# GPS_L70.net
KiCad netlist of a schematic drawn in Altium Designer
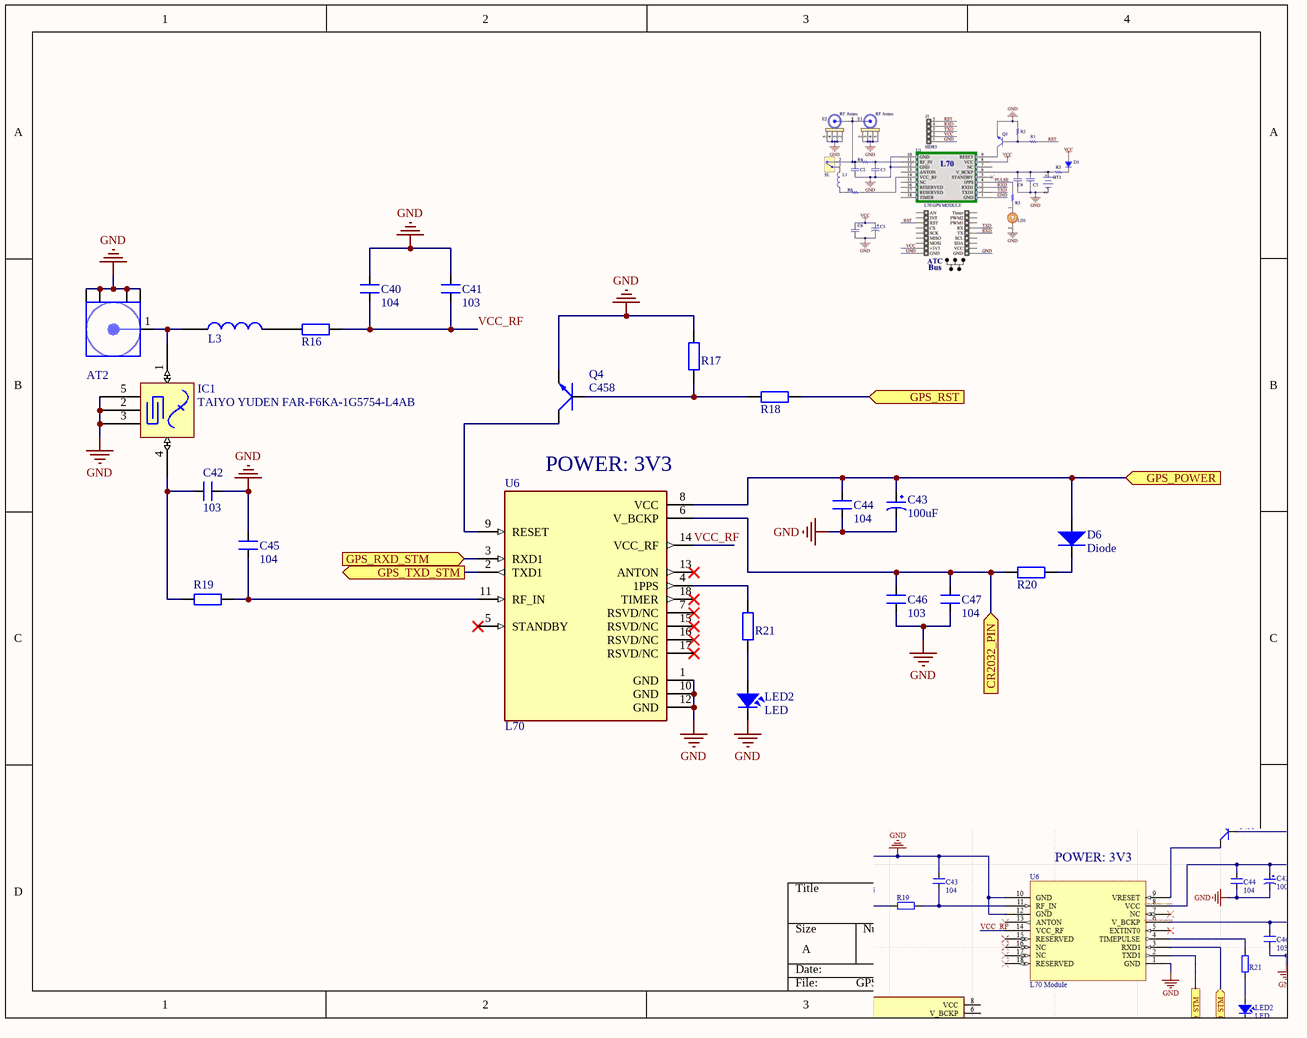
[diagram p0: GPS_L70.SchDoc]

(export (version "E")
  (design (tool "Eeschema 10.0.6"))
  (components
    (comp (ref "AT2")
      (value "AT-GSM-GPS")
      (footprint "SNW_H13-L17-SMA")
      (description "CONNECTER ANTENNA GPS GSM")
      (fields (field (name "MPN") "SNW_H13-L17-SMA") (field (name "MFR") "Sunny Way"))
      (libsource (lib "BYTECH_HW_LIB_2019 (1)") (part "SNW_H13-L17-SMA"))
    )
    (comp (ref "C40")
      (value "104")
      (footprint "CN2")
      (description "Cap np 104 => 105pF")
      (libsource (lib "KhanhBK_Library_4") (part "CN2"))
    )
    (comp (ref "C41")
      (value "103")
      (footprint "SM-0805")
      (description "Cap SMD")
      (libsource (lib "KhanhBK_Library_4") (part "CM"))
    )
    (comp (ref "C42")
      (value "103")
      (footprint "SM-0805")
      (description "Cap SMD")
      (libsource (lib "KhanhBK_Library_4") (part "CM"))
    )
    (comp (ref "C43")
      (value "100uF")
      (footprint "CP1/2.5")
      (description "C 47uF/50V , 220uF/16V")
      (libsource (lib "KhanhBK_Library_4") (part "CP2"))
    )
    (comp (ref "C44")
      (value "104")
      (footprint "CN2")
      (description "Cap np 104 => 105pF")
      (libsource (lib "KhanhBK_Library_4") (part "CN2"))
    )
    (comp (ref "C45")
      (value "104")
      (footprint "CN2")
      (description "Cap np 104 => 105pF")
      (libsource (lib "KhanhBK_Library_4") (part "CN2"))
    )
    (comp (ref "C46")
      (value "103")
      (footprint "SM-0805")
      (description "Cap SMD")
      (libsource (lib "KhanhBK_Library_4") (part "CM"))
    )
    (comp (ref "C47")
      (value "104")
      (footprint "CN2")
      (description "Cap np 104 => 105pF")
      (libsource (lib "KhanhBK_Library_4") (part "CN2"))
    )
    (comp (ref "D6")
      (value "Diode")
      (footprint "DIO-SMD-106")
      (libsource (lib "KhanhBK_Library_4") (part "Diode"))
    )
    (comp (ref "IC1")
      (value "TAIYO YUDEN FAR-F6KA-1G5754-L4AB")
      (footprint "TAIYO YUDEN SMD-5 1.4x1mm")
      (description "GPS SAW Filter Taiyo Yuden")
      (libsource (lib "KhanhBK_Library_4") (part "TAIYO YUDEN FAR-F6KA-1G5754-L4AB"))
    )
    (comp (ref "L3")
      (value "15uH/850mA")
      (footprint "IND-1210 (3225)")
      (description "FIXED IND 15UH 850MA 253.5 MOHM")
      (fields (field (name "MPN") "CBC3225T150KR") (field (name "MFR") "Taiyo Yuden"))
      (libsource (lib "BYTECH_HW_LIB_2019 (1)") (part "CBC3225T150KR"))
    )
    (comp (ref "LED2")
      (value "LED")
      (footprint "SM-LED-0805-Blue")
      (libsource (lib "KhanhBK_Library_4") (part "LED"))
    )
    (comp (ref "Q4")
      (value "C458")
      (footprint "SOT23-321")
      (description "NPN 600mW, ECB")
      (libsource (lib "KhanhBK_Library_4") (part "C458"))
    )
    (comp (ref "R16")
      (value "1k")
      (footprint "RES-SMD-0101")
      (description "Resistor R1/4W")
      (libsource (lib "KhanhBK_Library_4") (part "R"))
    )
    (comp (ref "R17")
      (value "1k")
      (footprint "RES-SMD-0101")
      (description "Resistor R1/4W")
      (libsource (lib "KhanhBK_Library_4") (part "R"))
    )
    (comp (ref "R18")
      (value "1k")
      (footprint "RES-SMD-0101")
      (description "Resistor R1/4W")
      (libsource (lib "KhanhBK_Library_4") (part "R"))
    )
    (comp (ref "R19")
      (value "1k")
      (footprint "RES-SMD-0101")
      (description "Resistor R1/4W")
      (libsource (lib "KhanhBK_Library_4") (part "R"))
    )
    (comp (ref "R20")
      (value "1k")
      (footprint "RES-SMD-0101")
      (description "Resistor R1/4W")
      (libsource (lib "KhanhBK_Library_4") (part "R"))
    )
    (comp (ref "R21")
      (value "1k")
      (footprint "RES-SMD-0101")
      (description "Resistor R1/4W")
      (libsource (lib "KhanhBK_Library_4") (part "R"))
    )
    (comp (ref "U6") (value "L70") (footprint "XCVR_L70") (libsource (lib "L70") (part "L70")))
  )
  (nets
    (net (code "1") (name "/CR2032_PIN") (class "Default")
      (node (ref "C46") (pin "1") (pinfunction "1_1") (pintype "passive"))
      (node (ref "C47") (pin "2") (pinfunction "2_2") (pintype "passive"))
      (node (ref "R20") (pin "2") (pinfunction "2_2") (pintype "passive"))
      (node (ref "U6") (pin "6") (pinfunction "V_BCKP_6") (pintype "power_in"))
    )
    (net (code "2") (name "/GPS_POWER") (class "Default")
      (node (ref "C43") (pin "1") (pinfunction "1_1") (pintype "passive"))
      (node (ref "C44") (pin "2") (pinfunction "2_2") (pintype "passive"))
      (node (ref "D6") (pin "1") (pinfunction "1_1") (pintype "passive"))
      (node (ref "U6") (pin "8") (pinfunction "VCC_8") (pintype "power_in"))
    )
    (net (code "3") (name "/GPS_RST") (class "Default")
      (node (ref "R18") (pin "1") (pinfunction "1_1") (pintype "passive"))
    )
    (net (code "4") (name "/GPS_RXD_STM") (class "Default")
      (node (ref "U6") (pin "3") (pinfunction "RXD1_3") (pintype "input"))
    )
    (net (code "5") (name "/GPS_TXD_STM") (class "Default")
      (node (ref "U6") (pin "2") (pinfunction "TXD1_2") (pintype "output"))
    )
    (net (code "6") (name "/VCC_RF") (class "Default")
      (node (ref "C40") (pin "2") (pinfunction "2_2") (pintype "passive"))
      (node (ref "C41") (pin "1") (pinfunction "1_1") (pintype "passive"))
      (node (ref "R16") (pin "2") (pinfunction "2_2") (pintype "passive"))
      (node (ref "U6") (pin "14") (pinfunction "VCC_RF_14") (pintype "output"))
    )
    (net (code "7") (name "GND") (class "Default")
      (node (ref "AT2") (pin "2") (pinfunction "2_2") (pintype "power_in"))
      (node (ref "C40") (pin "1") (pinfunction "1_1") (pintype "passive"))
      (node (ref "C41") (pin "2") (pinfunction "2_2") (pintype "passive"))
      (node (ref "C42") (pin "1") (pinfunction "1_1") (pintype "passive"))
      (node (ref "C43") (pin "2") (pinfunction "2_2") (pintype "passive"))
      (node (ref "C44") (pin "1") (pinfunction "1_1") (pintype "passive"))
      (node (ref "C45") (pin "2") (pinfunction "2_2") (pintype "passive"))
      (node (ref "C46") (pin "2") (pinfunction "2_2") (pintype "passive"))
      (node (ref "C47") (pin "1") (pinfunction "1_1") (pintype "passive"))
      (node (ref "IC1") (pin "2") (pinfunction "GND_2") (pintype "passive"))
      (node (ref "IC1") (pin "3") (pinfunction "GND_3") (pintype "passive"))
      (node (ref "IC1") (pin "5") (pinfunction "GND_5") (pintype "passive"))
      (node (ref "LED2") (pin "2") (pinfunction "2_2") (pintype "passive"))
      (node (ref "Q4") (pin "1") (pinfunction "E_1") (pintype "passive"))
      (node (ref "R17") (pin "2") (pinfunction "2_2") (pintype "passive"))
      (node (ref "U6") (pin "1") (pinfunction "GND_1") (pintype "power_in"))
      (node (ref "U6") (pin "10") (pinfunction "GND_10") (pintype "power_in"))
      (node (ref "U6") (pin "12") (pinfunction "GND_12") (pintype "power_in"))
    )
    (net (code "8") (name "Net-(AT2-Signal)") (class "Default")
      (node (ref "AT2") (pin "1") (pinfunction "Signal_1") (pintype "passive"))
      (node (ref "IC1") (pin "1") (pinfunction "IN_1") (pintype "bidirectional"))
      (node (ref "L3") (pin "1") (pinfunction "1_1") (pintype "passive"))
    )
    (net (code "9") (name "Net-(D6-Pad2)") (class "Default")
      (node (ref "D6") (pin "2") (pinfunction "2_2") (pintype "passive"))
      (node (ref "R20") (pin "1") (pinfunction "1_1") (pintype "passive"))
    )
    (net (code "10") (name "Net-(IC1-OUT)") (class "Default")
      (node (ref "C42") (pin "2") (pinfunction "2_2") (pintype "passive"))
      (node (ref "IC1") (pin "4") (pinfunction "OUT_4") (pintype "bidirectional"))
      (node (ref "R19") (pin "1") (pinfunction "1_1") (pintype "passive"))
    )
    (net (code "11") (name "Net-(L3-Pad2)") (class "Default")
      (node (ref "L3") (pin "2") (pinfunction "2_2") (pintype "passive"))
      (node (ref "R16") (pin "1") (pinfunction "1_1") (pintype "passive"))
    )
    (net (code "12") (name "Net-(LED2-Pad1)") (class "Default")
      (node (ref "LED2") (pin "1") (pinfunction "1_1") (pintype "passive"))
      (node (ref "R21") (pin "2") (pinfunction "2_2") (pintype "passive"))
    )
    (net (code "13") (name "Net-(Q4-B)") (class "Default")
      (node (ref "Q4") (pin "3") (pinfunction "B_3") (pintype "passive"))
      (node (ref "R17") (pin "1") (pinfunction "1_1") (pintype "passive"))
      (node (ref "R18") (pin "2") (pinfunction "2_2") (pintype "passive"))
    )
    (net (code "14") (name "Net-(Q4-C)") (class "Default")
      (node (ref "Q4") (pin "2") (pinfunction "C_2") (pintype "passive"))
      (node (ref "U6") (pin "9") (pinfunction "RESET_9") (pintype "input"))
    )
    (net (code "15") (name "Net-(U6-1PPS)") (class "Default")
      (node (ref "R21") (pin "1") (pinfunction "1_1") (pintype "passive"))
      (node (ref "U6") (pin "4") (pinfunction "1PPS_4") (pintype "output"))
    )
    (net (code "16") (name "Net-(U6-RF_IN)") (class "Default")
      (node (ref "C45") (pin "1") (pinfunction "1_1") (pintype "passive"))
      (node (ref "R19") (pin "2") (pinfunction "2_2") (pintype "passive"))
      (node (ref "U6") (pin "11") (pinfunction "RF_IN_11") (pintype "input"))
    )
    (net (code "17") (name "unconnected-(AT2-Pad2)") (class "Default")
      (node (ref "AT2") (pin "2") (pinfunction "2_2") (pintype "passive"))
    )
    (net (code "18") (name "unconnected-(U6-ANTON-Pad13)") (class "Default")
      (node (ref "U6") (pin "13") (pinfunction "ANTON_13") (pintype "output+no_connect"))
    )
    (net (code "19") (name "unconnected-(U6-RSVD{slash}NC-Pad7)") (class "Default")
      (node (ref "U6") (pin "7") (pinfunction "RSVD/NC_7") (pintype "passive+no_connect"))
    )
    (net (code "20") (name "unconnected-(U6-RSVD{slash}NC-Pad15)") (class "Default")
      (node (ref "U6") (pin "15") (pinfunction "RSVD/NC_15") (pintype "passive+no_connect"))
    )
    (net (code "21") (name "unconnected-(U6-RSVD{slash}NC-Pad16)") (class "Default")
      (node (ref "U6") (pin "16") (pinfunction "RSVD/NC_16") (pintype "passive+no_connect"))
    )
    (net (code "22") (name "unconnected-(U6-RSVD{slash}NC-Pad17)") (class "Default")
      (node (ref "U6") (pin "17") (pinfunction "RSVD/NC_17") (pintype "passive+no_connect"))
    )
    (net (code "23") (name "unconnected-(U6-STANDBY-Pad5)") (class "Default")
      (node (ref "U6") (pin "5") (pinfunction "STANDBY_5") (pintype "input+no_connect"))
    )
    (net (code "24") (name "unconnected-(U6-TIMER-Pad18)") (class "Default")
      (node (ref "U6") (pin "18") (pinfunction "TIMER_18") (pintype "output+no_connect"))
    )
  )
)
